# address_decoder_v2.net
KiCad netlist of a schematic drawn in EAGLE
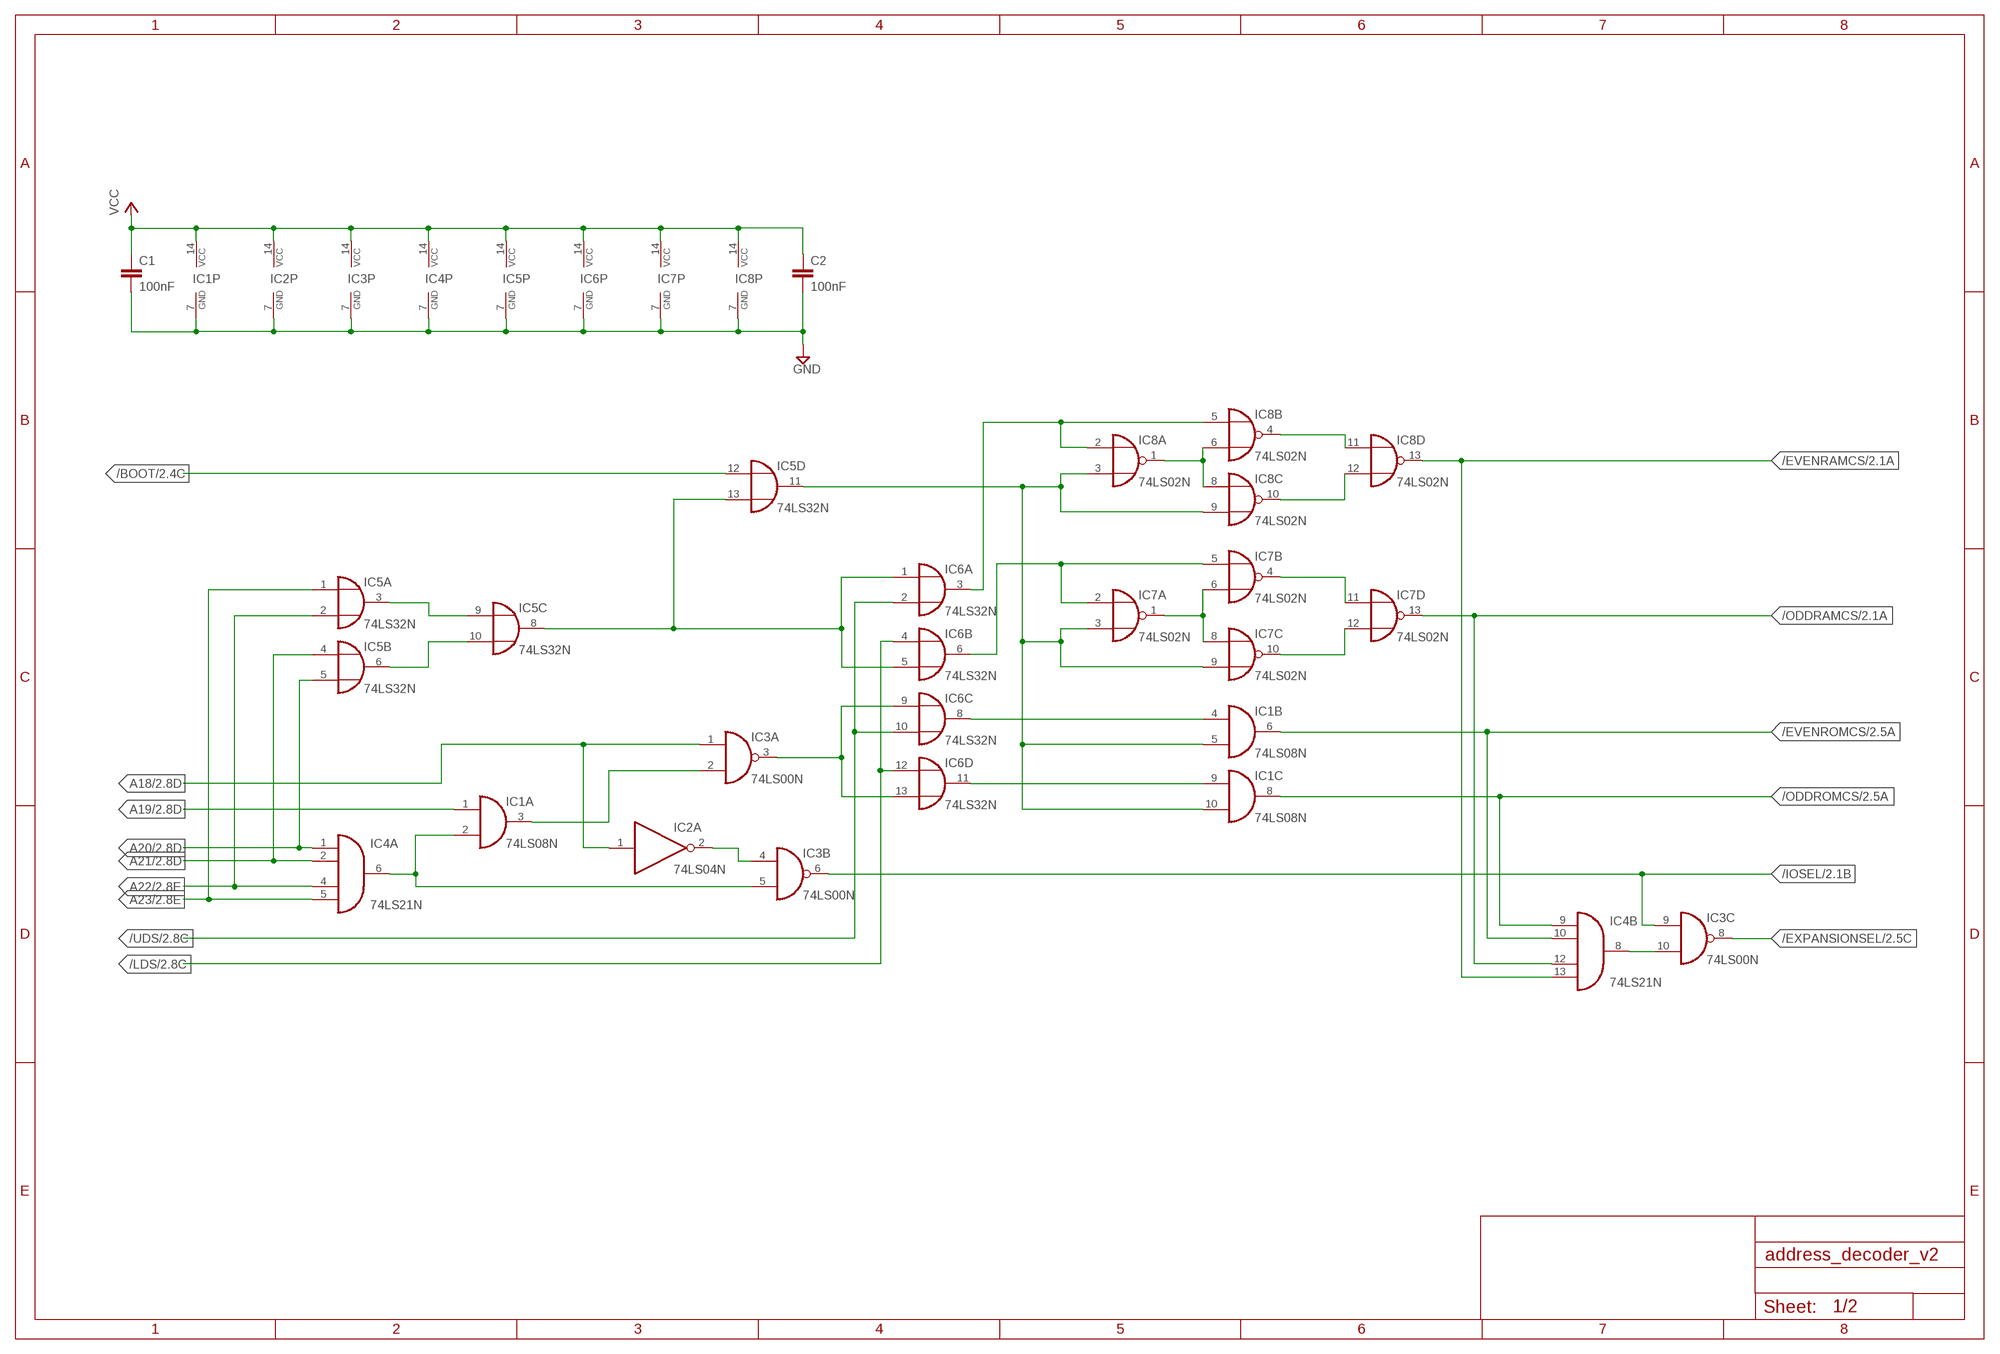
[diagram p0: schematic, sheet 1]
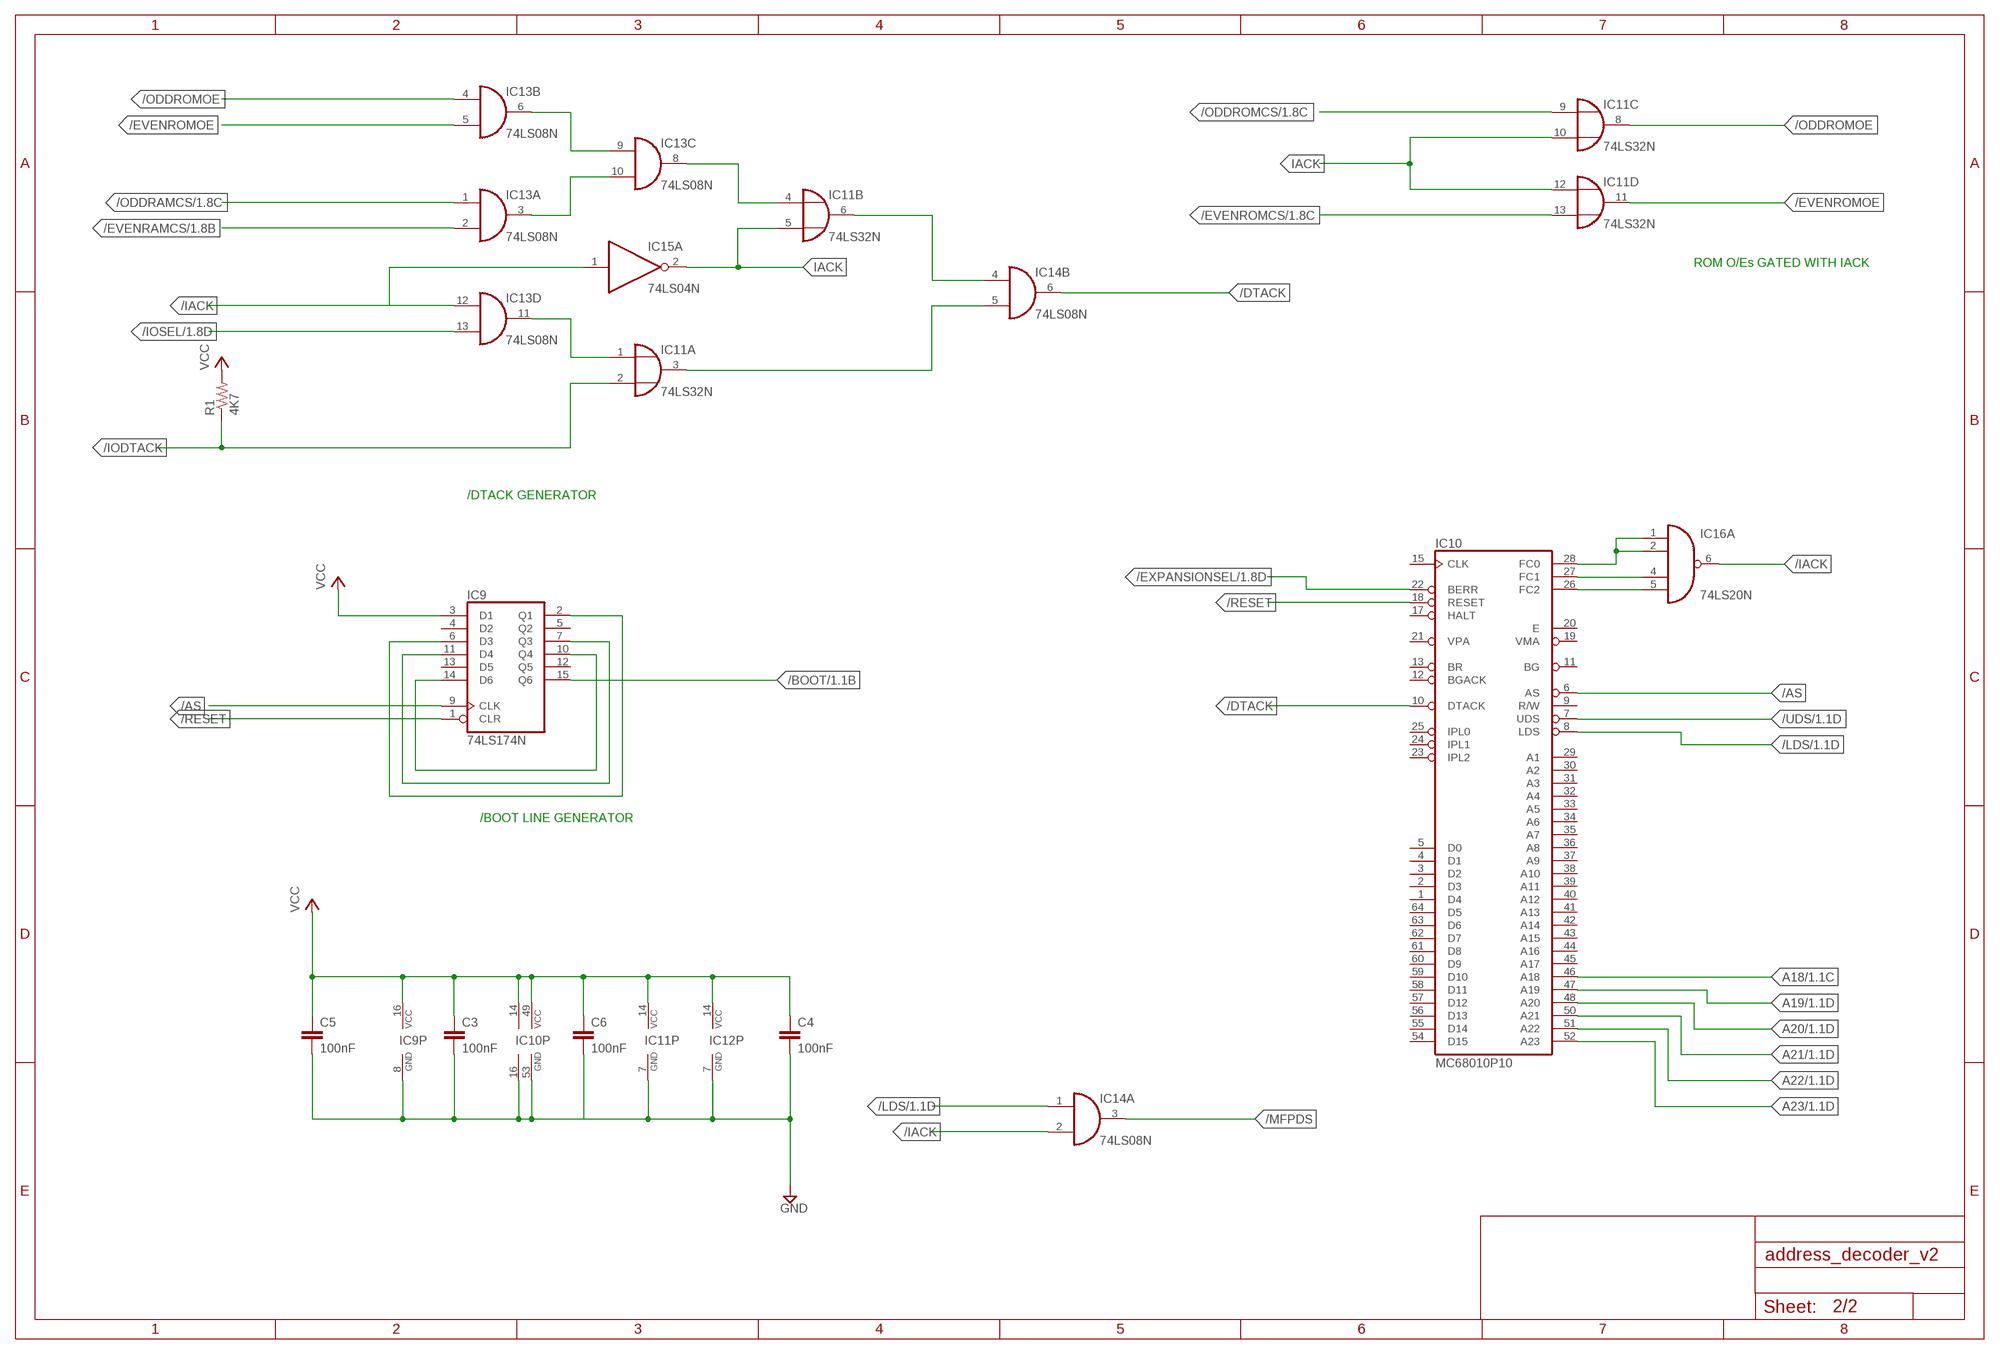
[diagram p1: schematic, sheet 2]

(export (version "E")
  (design (tool "Eeschema 10.0.6"))
  (components
    (comp (ref "C3")
      (value "100nF")
      (footprint "eagle-import:C5B3")
      (libsource (lib "eagle-import") (part "C5/3"))
    )
    (comp (ref "C4")
      (value "100nF")
      (footprint "eagle-import:C5B3")
      (libsource (lib "eagle-import") (part "C5/3"))
    )
    (comp (ref "C5")
      (value "100nF")
      (footprint "eagle-import:C5B3")
      (libsource (lib "eagle-import") (part "C5/3"))
    )
    (comp (ref "C6")
      (value "100nF")
      (footprint "eagle-import:C5B3")
      (libsource (lib "eagle-import") (part "C5/3"))
    )
    (comp (ref "IC9")
      (value "74LS174N")
      (footprint "eagle-import:DIL16")
      (libsource (lib "eagle-import") (part "74174NLS"))
    )
    (comp (ref "IC10")
      (value "MC68010P10")
      (footprint "eagle-import:DIL64")
      (libsource (lib "eagle-import") (part "MC68000P"))
    )
    (comp (ref "IC11")
      (value "74LS32N")
      (footprint "eagle-import:DIL14")
      (libsource (lib "eagle-import") (part "7432NLS"))
    )
    (comp (ref "IC12")
      (value "74LS21N")
      (footprint "eagle-import:DIL14")
      (libsource (lib "eagle-import") (part "7421NLS"))
    )
    (comp (ref "IC13")
      (value "74LS08N")
      (footprint "eagle-import:DIL14")
      (libsource (lib "eagle-import") (part "7408NLS"))
    )
    (comp (ref "IC14")
      (value "74LS08N")
      (footprint "eagle-import:DIL14")
      (libsource (lib "eagle-import") (part "7408NLS"))
    )
    (comp (ref "IC15")
      (value "74LS04N")
      (footprint "eagle-import:DIL14")
      (libsource (lib "eagle-import") (part "7404NLS"))
    )
    (comp (ref "IC16")
      (value "74LS20N")
      (footprint "eagle-import:DIL14")
      (libsource (lib "eagle-import") (part "7420NLS"))
    )
    (comp (ref "R1")
      (value "4K7")
      (footprint "eagle-import:0204_7")
      (libsource (lib "eagle-import") (part "R-US_0204/7"))
    )
    (comp (ref "C1")
      (value "100nF")
      (footprint "eagle-import:C025-024X044")
      (libsource (lib "eagle-import") (part "C-EU025-024X044"))
    )
    (comp (ref "C2")
      (value "100nF")
      (footprint "eagle-import:C025-024X044")
      (libsource (lib "eagle-import") (part "C-EU025-024X044"))
    )
    (comp (ref "IC1")
      (value "74LS08N")
      (footprint "eagle-import:DIL14")
      (fields (field (name "SPICEPREFIX") "I"))
      (libsource (lib "eagle-import") (part "7408NLS"))
    )
    (comp (ref "IC2")
      (value "74LS04N")
      (footprint "eagle-import:DIL14")
      (fields (field (name "SPICEPREFIX") "I"))
      (libsource (lib "eagle-import") (part "7404NLS"))
    )
    (comp (ref "IC3")
      (value "74LS00N")
      (footprint "eagle-import:DIL14")
      (libsource (lib "eagle-import") (part "7400NLS"))
    )
    (comp (ref "IC4")
      (value "74LS21N")
      (footprint "eagle-import:DIL14")
      (fields (field (name "SPICEPREFIX") "X"))
      (libsource (lib "eagle-import") (part "7421NLS"))
    )
    (comp (ref "IC5")
      (value "74LS32N")
      (footprint "eagle-import:DIL14")
      (fields (field (name "SPICEPREFIX") "J"))
      (libsource (lib "eagle-import") (part "7432NLS"))
    )
    (comp (ref "IC6")
      (value "74LS32N")
      (footprint "eagle-import:DIL14")
      (libsource (lib "eagle-import") (part "7432NLS"))
    )
    (comp (ref "IC7")
      (value "74LS02N")
      (footprint "eagle-import:DIL14")
      (libsource (lib "eagle-import") (part "7402NLS"))
    )
    (comp (ref "IC8")
      (value "74LS02N")
      (footprint "eagle-import:DIL14")
      (libsource (lib "eagle-import") (part "7402NLS"))
    )
  )
  (nets
    (net (code "1") (name "A18") (class "Default")
      (node (ref "IC10") (pin "46") (pinfunction "A18_46") (pintype "output"))
      (node (ref "IC2") (pin "1") (pinfunction "I_1") (pintype "input"))
      (node (ref "IC3") (pin "1") (pinfunction "I0_1") (pintype "input"))
    )
    (net (code "2") (name "A19") (class "Default")
      (node (ref "IC1") (pin "1") (pinfunction "I0_1") (pintype "input"))
      (node (ref "IC10") (pin "47") (pinfunction "A19_47") (pintype "output"))
    )
    (net (code "3") (name "A20") (class "Default")
      (node (ref "IC10") (pin "48") (pinfunction "A20_48") (pintype "output"))
      (node (ref "IC4") (pin "1") (pinfunction "I0_1") (pintype "input"))
      (node (ref "IC5") (pin "5") (pinfunction "I1_5") (pintype "input"))
    )
    (net (code "4") (name "A21") (class "Default")
      (node (ref "IC10") (pin "50") (pinfunction "A21_50") (pintype "output"))
      (node (ref "IC4") (pin "2") (pinfunction "I1_2") (pintype "input"))
      (node (ref "IC5") (pin "4") (pinfunction "I0_4") (pintype "input"))
    )
    (net (code "5") (name "A22") (class "Default")
      (node (ref "IC10") (pin "51") (pinfunction "A22_51") (pintype "output"))
      (node (ref "IC4") (pin "4") (pinfunction "I2_4") (pintype "input"))
      (node (ref "IC5") (pin "2") (pinfunction "I1_2") (pintype "input"))
    )
    (net (code "6") (name "A23") (class "Default")
      (node (ref "IC10") (pin "52") (pinfunction "A23_52") (pintype "output"))
      (node (ref "IC4") (pin "5") (pinfunction "I3_5") (pintype "input"))
      (node (ref "IC5") (pin "1") (pinfunction "I0_1") (pintype "input"))
    )
    (net (code "7") (name "GND") (class "Default")
      (node (ref "C1") (pin "2") (pinfunction "2_2") (pintype "passive"))
      (node (ref "C2") (pin "2") (pinfunction "2_2") (pintype "passive"))
      (node (ref "C3") (pin "2") (pinfunction "2_2") (pintype "passive"))
      (node (ref "C4") (pin "2") (pinfunction "2_2") (pintype "passive"))
      (node (ref "C5") (pin "2") (pinfunction "2_2") (pintype "passive"))
      (node (ref "IC1") (pin "7") (pinfunction "GND_7") (pintype "power_in"))
      (node (ref "IC10") (pin "16") (pinfunction "GND_16") (pintype "power_in"))
      (node (ref "IC10") (pin "53") (pinfunction "GND_53") (pintype "power_in"))
      (node (ref "IC11") (pin "7") (pinfunction "GND_7") (pintype "power_in"))
      (node (ref "IC12") (pin "7") (pinfunction "GND_7") (pintype "power_in"))
      (node (ref "IC2") (pin "7") (pinfunction "GND_7") (pintype "power_in"))
      (node (ref "IC3") (pin "7") (pinfunction "GND_7") (pintype "power_in"))
      (node (ref "IC4") (pin "7") (pinfunction "GND_7") (pintype "power_in"))
      (node (ref "IC5") (pin "7") (pinfunction "GND_7") (pintype "power_in"))
      (node (ref "IC6") (pin "7") (pinfunction "GND_7") (pintype "power_in"))
      (node (ref "IC7") (pin "7") (pinfunction "GND_7") (pintype "power_in"))
      (node (ref "IC8") (pin "7") (pinfunction "GND_7") (pintype "power_in"))
      (node (ref "IC9") (pin "8") (pinfunction "GND_8") (pintype "power_in"))
    )
    (net (code "8") (name "IACK") (class "Default")
      (node (ref "IC11") (pin "10") (pinfunction "I1_10") (pintype "input"))
      (node (ref "IC11") (pin "12") (pinfunction "I0_12") (pintype "input"))
      (node (ref "IC11") (pin "5") (pinfunction "I1_5") (pintype "input"))
      (node (ref "IC15") (pin "2") (pinfunction "O_2") (pintype "output"))
    )
    (net (code "9") (name "Net-(IC1A-I1)") (class "Default")
      (node (ref "IC1") (pin "2") (pinfunction "I1_2") (pintype "input"))
      (node (ref "IC3") (pin "5") (pinfunction "I1_5") (pintype "input"))
      (node (ref "IC4") (pin "6") (pinfunction "O_6") (pintype "output"))
    )
    (net (code "10") (name "Net-(IC1A-O)") (class "Default")
      (node (ref "IC1") (pin "3") (pinfunction "O_3") (pintype "output"))
      (node (ref "IC3") (pin "2") (pinfunction "I1_2") (pintype "input"))
    )
    (net (code "11") (name "Net-(IC1B-I0)") (class "Default")
      (node (ref "IC1") (pin "4") (pinfunction "I0_4") (pintype "input"))
      (node (ref "IC6") (pin "8") (pinfunction "O_8") (pintype "output"))
    )
    (net (code "12") (name "Net-(IC1B-I1)") (class "Default")
      (node (ref "IC1") (pin "10") (pinfunction "I1_10") (pintype "input"))
      (node (ref "IC1") (pin "5") (pinfunction "I1_5") (pintype "input"))
      (node (ref "IC5") (pin "11") (pinfunction "O_11") (pintype "output"))
      (node (ref "IC7") (pin "3") (pinfunction "I1_3") (pintype "input"))
      (node (ref "IC7") (pin "9") (pinfunction "I1_9") (pintype "input"))
      (node (ref "IC8") (pin "3") (pinfunction "I1_3") (pintype "input"))
      (node (ref "IC8") (pin "9") (pinfunction "I1_9") (pintype "input"))
    )
    (net (code "13") (name "Net-(IC1C-I0)") (class "Default")
      (node (ref "IC1") (pin "9") (pinfunction "I0_9") (pintype "input"))
      (node (ref "IC6") (pin "11") (pinfunction "O_11") (pintype "output"))
    )
    (net (code "14") (name "Net-(IC2A-O)") (class "Default")
      (node (ref "IC2") (pin "2") (pinfunction "O_2") (pintype "output"))
      (node (ref "IC3") (pin "4") (pinfunction "I0_4") (pintype "input"))
    )
    (net (code "15") (name "Net-(IC3A-O)") (class "Default")
      (node (ref "IC3") (pin "3") (pinfunction "O_3") (pintype "output"))
      (node (ref "IC6") (pin "13") (pinfunction "I1_13") (pintype "input"))
      (node (ref "IC6") (pin "9") (pinfunction "I0_9") (pintype "input"))
    )
    (net (code "16") (name "Net-(IC3C-I1)") (class "Default")
      (node (ref "IC3") (pin "10") (pinfunction "I1_10") (pintype "input"))
      (node (ref "IC4") (pin "8") (pinfunction "O_8") (pintype "output"))
    )
    (net (code "17") (name "Net-(IC5A-O)") (class "Default")
      (node (ref "IC5") (pin "3") (pinfunction "O_3") (pintype "output"))
      (node (ref "IC5") (pin "9") (pinfunction "I0_9") (pintype "input"))
    )
    (net (code "18") (name "Net-(IC5B-O)") (class "Default")
      (node (ref "IC5") (pin "10") (pinfunction "I1_10") (pintype "input"))
      (node (ref "IC5") (pin "6") (pinfunction "O_6") (pintype "output"))
    )
    (net (code "19") (name "Net-(IC5C-O)") (class "Default")
      (node (ref "IC5") (pin "13") (pinfunction "I1_13") (pintype "input"))
      (node (ref "IC5") (pin "8") (pinfunction "O_8") (pintype "output"))
      (node (ref "IC6") (pin "1") (pinfunction "I0_1") (pintype "input"))
      (node (ref "IC6") (pin "5") (pinfunction "I1_5") (pintype "input"))
    )
    (net (code "20") (name "Net-(IC6A-O)") (class "Default")
      (node (ref "IC6") (pin "3") (pinfunction "O_3") (pintype "output"))
      (node (ref "IC8") (pin "2") (pinfunction "I0_2") (pintype "input"))
      (node (ref "IC8") (pin "5") (pinfunction "I0_5") (pintype "input"))
    )
    (net (code "21") (name "Net-(IC6B-O)") (class "Default")
      (node (ref "IC6") (pin "6") (pinfunction "O_6") (pintype "output"))
      (node (ref "IC7") (pin "2") (pinfunction "I0_2") (pintype "input"))
      (node (ref "IC7") (pin "5") (pinfunction "I0_5") (pintype "input"))
    )
    (net (code "22") (name "Net-(IC7A-O)") (class "Default")
      (node (ref "IC7") (pin "1") (pinfunction "O_1") (pintype "output"))
      (node (ref "IC7") (pin "6") (pinfunction "I1_6") (pintype "input"))
      (node (ref "IC7") (pin "8") (pinfunction "I0_8") (pintype "input"))
    )
    (net (code "23") (name "Net-(IC7B-O)") (class "Default")
      (node (ref "IC7") (pin "11") (pinfunction "I0_11") (pintype "input"))
      (node (ref "IC7") (pin "4") (pinfunction "O_4") (pintype "output"))
    )
    (net (code "24") (name "Net-(IC7C-O)") (class "Default")
      (node (ref "IC7") (pin "10") (pinfunction "O_10") (pintype "output"))
      (node (ref "IC7") (pin "12") (pinfunction "I1_12") (pintype "input"))
    )
    (net (code "25") (name "Net-(IC8A-O)") (class "Default")
      (node (ref "IC8") (pin "1") (pinfunction "O_1") (pintype "output"))
      (node (ref "IC8") (pin "6") (pinfunction "I1_6") (pintype "input"))
      (node (ref "IC8") (pin "8") (pinfunction "I0_8") (pintype "input"))
    )
    (net (code "26") (name "Net-(IC8B-O)") (class "Default")
      (node (ref "IC8") (pin "11") (pinfunction "I0_11") (pintype "input"))
      (node (ref "IC8") (pin "4") (pinfunction "O_4") (pintype "output"))
    )
    (net (code "27") (name "Net-(IC8C-O)") (class "Default")
      (node (ref "IC8") (pin "10") (pinfunction "O_10") (pintype "output"))
      (node (ref "IC8") (pin "12") (pinfunction "I1_12") (pintype "input"))
    )
    (net (code "28") (name "Net-(IC9A-D3)") (class "Default")
      (node (ref "IC9") (pin "2") (pinfunction "Q1_2") (pintype "output"))
      (node (ref "IC9") (pin "6") (pinfunction "D3_6") (pintype "input"))
    )
    (net (code "29") (name "Net-(IC9A-D4)") (class "Default")
      (node (ref "IC9") (pin "11") (pinfunction "D4_11") (pintype "input"))
      (node (ref "IC9") (pin "7") (pinfunction "Q3_7") (pintype "output"))
    )
    (net (code "30") (name "Net-(IC9A-D6)") (class "Default")
      (node (ref "IC9") (pin "10") (pinfunction "Q4_10") (pintype "output"))
      (node (ref "IC9") (pin "14") (pinfunction "D6_14") (pintype "input"))
    )
    (net (code "31") (name "Net-(IC10A-FC0)") (class "Default")
      (node (ref "IC10") (pin "28") (pinfunction "FC0_28") (pintype "output"))
      (node (ref "IC16") (pin "1") (pinfunction "I0_1") (pintype "input"))
      (node (ref "IC16") (pin "2") (pinfunction "I1_2") (pintype "input"))
    )
    (net (code "32") (name "Net-(IC10A-FC1)") (class "Default")
      (node (ref "IC10") (pin "27") (pinfunction "FC1_27") (pintype "output"))
      (node (ref "IC16") (pin "4") (pinfunction "I2_4") (pintype "input"))
    )
    (net (code "33") (name "Net-(IC10A-FC2)") (class "Default")
      (node (ref "IC10") (pin "26") (pinfunction "FC2_26") (pintype "output"))
      (node (ref "IC16") (pin "5") (pinfunction "I3_5") (pintype "input"))
    )
    (net (code "34") (name "Net-(IC11A-I0)") (class "Default")
      (node (ref "IC11") (pin "1") (pinfunction "I0_1") (pintype "input"))
      (node (ref "IC13") (pin "11") (pinfunction "O_11") (pintype "output"))
    )
    (net (code "35") (name "Net-(IC11A-O)") (class "Default")
      (node (ref "IC11") (pin "3") (pinfunction "O_3") (pintype "output"))
      (node (ref "IC14") (pin "5") (pinfunction "I1_5") (pintype "input"))
    )
    (net (code "36") (name "Net-(IC11B-I0)") (class "Default")
      (node (ref "IC11") (pin "4") (pinfunction "I0_4") (pintype "input"))
      (node (ref "IC13") (pin "8") (pinfunction "O_8") (pintype "output"))
    )
    (net (code "37") (name "Net-(IC11B-O)") (class "Default")
      (node (ref "IC11") (pin "6") (pinfunction "O_6") (pintype "output"))
      (node (ref "IC14") (pin "4") (pinfunction "I0_4") (pintype "input"))
    )
    (net (code "38") (name "Net-(IC13A-O)") (class "Default")
      (node (ref "IC13") (pin "10") (pinfunction "I1_10") (pintype "input"))
      (node (ref "IC13") (pin "3") (pinfunction "O_3") (pintype "output"))
    )
    (net (code "39") (name "Net-(IC13B-O)") (class "Default")
      (node (ref "IC13") (pin "6") (pinfunction "O_6") (pintype "output"))
      (node (ref "IC13") (pin "9") (pinfunction "I0_9") (pintype "input"))
    )
    (net (code "40") (name "VCC") (class "Default")
      (node (ref "C1") (pin "1") (pinfunction "1_1") (pintype "passive"))
      (node (ref "C2") (pin "1") (pinfunction "1_1") (pintype "passive"))
      (node (ref "C3") (pin "1") (pinfunction "1_1") (pintype "passive"))
      (node (ref "C4") (pin "1") (pinfunction "1_1") (pintype "passive"))
      (node (ref "C5") (pin "1") (pinfunction "1_1") (pintype "passive"))
      (node (ref "C6") (pin "1") (pinfunction "1_1") (pintype "passive"))
      (node (ref "IC1") (pin "14") (pinfunction "VCC_14") (pintype "power_in"))
      (node (ref "IC10") (pin "14") (pinfunction "VCC_14") (pintype "power_in"))
      (node (ref "IC10") (pin "49") (pinfunction "VCC_49") (pintype "power_in"))
      (node (ref "IC11") (pin "14") (pinfunction "VCC_14") (pintype "power_in"))
      (node (ref "IC12") (pin "14") (pinfunction "VCC_14") (pintype "power_in"))
      (node (ref "IC2") (pin "14") (pinfunction "VCC_14") (pintype "power_in"))
      (node (ref "IC3") (pin "14") (pinfunction "VCC_14") (pintype "power_in"))
      (node (ref "IC4") (pin "14") (pinfunction "VCC_14") (pintype "power_in"))
      (node (ref "IC5") (pin "14") (pinfunction "VCC_14") (pintype "power_in"))
      (node (ref "IC6") (pin "14") (pinfunction "VCC_14") (pintype "power_in"))
      (node (ref "IC7") (pin "14") (pinfunction "VCC_14") (pintype "power_in"))
      (node (ref "IC8") (pin "14") (pinfunction "VCC_14") (pintype "power_in"))
      (node (ref "IC9") (pin "16") (pinfunction "VCC_16") (pintype "power_in"))
      (node (ref "IC9") (pin "3") (pinfunction "D1_3") (pintype "input"))
      (node (ref "R1") (pin "2") (pinfunction "2_2") (pintype "passive"))
    )
    (net (code "41") (name "unconnected-(C6-Pad2)") (class "Default")
      (node (ref "C6") (pin "2") (pinfunction "2_2") (pintype "passive"))
    )
    (net (code "42") (name "unconnected-(IC9A-D2-Pad4)") (class "Default")
      (node (ref "IC9") (pin "4") (pinfunction "D2_4") (pintype "input"))
    )
    (net (code "43") (name "unconnected-(IC9A-D5-Pad13)") (class "Default")
      (node (ref "IC9") (pin "13") (pinfunction "D5_13") (pintype "input"))
    )
    (net (code "44") (name "unconnected-(IC9A-Q2-Pad5)") (class "Default")
      (node (ref "IC9") (pin "5") (pinfunction "Q2_5") (pintype "output"))
    )
    (net (code "45") (name "unconnected-(IC9A-Q5-Pad12)") (class "Default")
      (node (ref "IC9") (pin "12") (pinfunction "Q5_12") (pintype "output"))
    )
    (net (code "46") (name "unconnected-(IC10A-A1-Pad29)") (class "Default")
      (node (ref "IC10") (pin "29") (pinfunction "A1_29") (pintype "output"))
    )
    (net (code "47") (name "unconnected-(IC10A-A2-Pad30)") (class "Default")
      (node (ref "IC10") (pin "30") (pinfunction "A2_30") (pintype "output"))
    )
    (net (code "48") (name "unconnected-(IC10A-A3-Pad31)") (class "Default")
      (node (ref "IC10") (pin "31") (pinfunction "A3_31") (pintype "output"))
    )
    (net (code "49") (name "unconnected-(IC10A-A4-Pad32)") (class "Default")
      (node (ref "IC10") (pin "32") (pinfunction "A4_32") (pintype "output"))
    )
    (net (code "50") (name "unconnected-(IC10A-A5-Pad33)") (class "Default")
      (node (ref "IC10") (pin "33") (pinfunction "A5_33") (pintype "output"))
    )
    (net (code "51") (name "unconnected-(IC10A-A6-Pad34)") (class "Default")
      (node (ref "IC10") (pin "34") (pinfunction "A6_34") (pintype "output"))
    )
    (net (code "52") (name "unconnected-(IC10A-A7-Pad35)") (class "Default")
      (node (ref "IC10") (pin "35") (pinfunction "A7_35") (pintype "output"))
    )
    (net (code "53") (name "unconnected-(IC10A-A8-Pad36)") (class "Default")
      (node (ref "IC10") (pin "36") (pinfunction "A8_36") (pintype "output"))
    )
    (net (code "54") (name "unconnected-(IC10A-A9-Pad37)") (class "Default")
      (node (ref "IC10") (pin "37") (pinfunction "A9_37") (pintype "output"))
    )
    (net (code "55") (name "unconnected-(IC10A-A10-Pad38)") (class "Default")
      (node (ref "IC10") (pin "38") (pinfunction "A10_38") (pintype "output"))
    )
    (net (code "56") (name "unconnected-(IC10A-A11-Pad39)") (class "Default")
      (node (ref "IC10") (pin "39") (pinfunction "A11_39") (pintype "output"))
    )
    (net (code "57") (name "unconnected-(IC10A-A12-Pad40)") (class "Default")
      (node (ref "IC10") (pin "40") (pinfunction "A12_40") (pintype "output"))
    )
    (net (code "58") (name "unconnected-(IC10A-A13-Pad41)") (class "Default")
      (node (ref "IC10") (pin "41") (pinfunction "A13_41") (pintype "output"))
    )
    (net (code "59") (name "unconnected-(IC10A-A14-Pad42)") (class "Default")
      (node (ref "IC10") (pin "42") (pinfunction "A14_42") (pintype "output"))
    )
    (net (code "60") (name "unconnected-(IC10A-A15-Pad43)") (class "Default")
      (node (ref "IC10") (pin "43") (pinfunction "A15_43") (pintype "output"))
    )
    (net (code "61") (name "unconnected-(IC10A-A16-Pad44)") (class "Default")
      (node (ref "IC10") (pin "44") (pinfunction "A16_44") (pintype "output"))
    )
    (net (code "62") (name "unconnected-(IC10A-A17-Pad45)") (class "Default")
      (node (ref "IC10") (pin "45") (pinfunction "A17_45") (pintype "output"))
    )
    (net (code "63") (name "unconnected-(IC10A-BG-Pad11)") (class "Default")
      (node (ref "IC10") (pin "11") (pinfunction "BG_11") (pintype "output"))
    )
    (net (code "64") (name "unconnected-(IC10A-BGACK-Pad12)") (class "Default")
      (node (ref "IC10") (pin "12") (pinfunction "BGACK_12") (pintype "input"))
    )
    (net (code "65") (name "unconnected-(IC10A-BR-Pad13)") (class "Default")
      (node (ref "IC10") (pin "13") (pinfunction "BR_13") (pintype "input"))
    )
    (net (code "66") (name "unconnected-(IC10A-CLK-Pad15)") (class "Default")
      (node (ref "IC10") (pin "15") (pinfunction "CLK_15") (pintype "input"))
    )
    (net (code "67") (name "unconnected-(IC10A-D0-Pad5)") (class "Default")
      (node (ref "IC10") (pin "5") (pinfunction "D0_5") (pintype "bidirectional"))
    )
    (net (code "68") (name "unconnected-(IC10A-D1-Pad4)") (class "Default")
      (node (ref "IC10") (pin "4") (pinfunction "D1_4") (pintype "bidirectional"))
    )
    (net (code "69") (name "unconnected-(IC10A-D2-Pad3)") (class "Default")
      (node (ref "IC10") (pin "3") (pinfunction "D2_3") (pintype "bidirectional"))
    )
    (net (code "70") (name "unconnected-(IC10A-D3-Pad2)") (class "Default")
      (node (ref "IC10") (pin "2") (pinfunction "D3_2") (pintype "bidirectional"))
    )
    (net (code "71") (name "unconnected-(IC10A-D4-Pad1)") (class "Default")
      (node (ref "IC10") (pin "1") (pinfunction "D4_1") (pintype "bidirectional"))
    )
    (net (code "72") (name "unconnected-(IC10A-D5-Pad64)") (class "Default")
      (node (ref "IC10") (pin "64") (pinfunction "D5_64") (pintype "bidirectional"))
    )
    (net (code "73") (name "unconnected-(IC10A-D6-Pad63)") (class "Default")
      (node (ref "IC10") (pin "63") (pinfunction "D6_63") (pintype "bidirectional"))
    )
    (net (code "74") (name "unconnected-(IC10A-D7-Pad62)") (class "Default")
      (node (ref "IC10") (pin "62") (pinfunction "D7_62") (pintype "bidirectional"))
    )
    (net (code "75") (name "unconnected-(IC10A-D8-Pad61)") (class "Default")
      (node (ref "IC10") (pin "61") (pinfunction "D8_61") (pintype "bidirectional"))
    )
    (net (code "76") (name "unconnected-(IC10A-D9-Pad60)") (class "Default")
      (node (ref "IC10") (pin "60") (pinfunction "D9_60") (pintype "bidirectional"))
    )
    (net (code "77") (name "unconnected-(IC10A-D10-Pad59)") (class "Default")
      (node (ref "IC10") (pin "59") (pinfunction "D10_59") (pintype "bidirectional"))
    )
    (net (code "78") (name "unconnected-(IC10A-D11-Pad58)") (class "Default")
      (node (ref "IC10") (pin "58") (pinfunction "D11_58") (pintype "bidirectional"))
    )
    (net (code "79") (name "unconnected-(IC10A-D12-Pad57)") (class "Default")
      (node (ref "IC10") (pin "57") (pinfunction "D12_57") (pintype "bidirectional"))
    )
    (net (code "80") (name "unconnected-(IC10A-D13-Pad56)") (class "Default")
      (node (ref "IC10") (pin "56") (pinfunction "D13_56") (pintype "bidirectional"))
    )
    (net (code "81") (name "unconnected-(IC10A-D14-Pad55)") (class "Default")
      (node (ref "IC10") (pin "55") (pinfunction "D14_55") (pintype "bidirectional"))
    )
    (net (code "82") (name "unconnected-(IC10A-D15-Pad54)") (class "Default")
      (node (ref "IC10") (pin "54") (pinfunction "D15_54") (pintype "bidirectional"))
    )
    (net (code "83") (name "unconnected-(IC10A-E-Pad20)") (class "Default")
      (node (ref "IC10") (pin "20") (pinfunction "E_20") (pintype "output"))
    )
    (net (code "84") (name "unconnected-(IC10A-HALT-Pad17)") (class "Default")
      (node (ref "IC10") (pin "17") (pinfunction "HALT_17") (pintype "bidirectional"))
    )
    (net (code "85") (name "unconnected-(IC10A-IPL0-Pad25)") (class "Default")
      (node (ref "IC10") (pin "25") (pinfunction "IPL0_25") (pintype "input"))
    )
    (net (code "86") (name "unconnected-(IC10A-IPL1-Pad24)") (class "Default")
      (node (ref "IC10") (pin "24") (pinfunction "IPL1_24") (pintype "input"))
    )
    (net (code "87") (name "unconnected-(IC10A-IPL2-Pad23)") (class "Default")
      (node (ref "IC10") (pin "23") (pinfunction "IPL2_23") (pintype "input"))
    )
    (net (code "88") (name "unconnected-(IC10A-R{slash}W-Pad9)") (class "Default")
      (node (ref "IC10") (pin "9") (pinfunction "R/W_9") (pintype "output"))
    )
    (net (code "89") (name "unconnected-(IC10A-VMA-Pad19)") (class "Default")
      (node (ref "IC10") (pin "19") (pinfunction "VMA_19") (pintype "output"))
    )
    (net (code "90") (name "unconnected-(IC10A-VPA-Pad21)") (class "Default")
      (node (ref "IC10") (pin "21") (pinfunction "VPA_21") (pintype "input"))
    )
    (net (code "91") (name "{slash}AS") (class "Default")
      (node (ref "IC10") (pin "6") (pinfunction "AS_6") (pintype "output"))
      (node (ref "IC9") (pin "9") (pinfunction "CLK_9") (pintype "input"))
    )
    (net (code "92") (name "{slash}BOOT") (class "Default")
      (node (ref "IC5") (pin "12") (pinfunction "I0_12") (pintype "input"))
      (node (ref "IC9") (pin "15") (pinfunction "Q6_15") (pintype "output"))
    )
    (net (code "93") (name "{slash}DTACK") (class "Default")
      (node (ref "IC10") (pin "10") (pinfunction "DTACK_10") (pintype "input"))
      (node (ref "IC14") (pin "6") (pinfunction "O_6") (pintype "output"))
    )
    (net (code "94") (name "{slash}EVENRAMCS") (class "Default")
      (node (ref "IC13") (pin "2") (pinfunction "I1_2") (pintype "input"))
      (node (ref "IC4") (pin "13") (pinfunction "I3_13") (pintype "input"))
      (node (ref "IC8") (pin "13") (pinfunction "O_13") (pintype "output"))
    )
    (net (code "95") (name "{slash}EVENROMCS") (class "Default")
      (node (ref "IC1") (pin "6") (pinfunction "O_6") (pintype "output"))
      (node (ref "IC11") (pin "13") (pinfunction "I1_13") (pintype "input"))
      (node (ref "IC4") (pin "10") (pinfunction "I1_10") (pintype "input"))
    )
    (net (code "96") (name "{slash}EVENROMOE") (class "Default")
      (node (ref "IC11") (pin "11") (pinfunction "O_11") (pintype "output"))
      (node (ref "IC13") (pin "5") (pinfunction "I1_5") (pintype "input"))
    )
    (net (code "97") (name "{slash}EXPANSIONSEL") (class "Default")
      (node (ref "IC10") (pin "22") (pinfunction "BERR_22") (pintype "input"))
      (node (ref "IC3") (pin "8") (pinfunction "O_8") (pintype "output"))
    )
    (net (code "98") (name "{slash}IACK") (class "Default")
      (node (ref "IC13") (pin "12") (pinfunction "I0_12") (pintype "input"))
      (node (ref "IC14") (pin "2") (pinfunction "I1_2") (pintype "input"))
      (node (ref "IC15") (pin "1") (pinfunction "I_1") (pintype "input"))
      (node (ref "IC16") (pin "6") (pinfunction "O_6") (pintype "output"))
    )
    (net (code "99") (name "{slash}IODTACK") (class "Default")
      (node (ref "IC11") (pin "2") (pinfunction "I1_2") (pintype "input"))
      (node (ref "R1") (pin "1") (pinfunction "1_1") (pintype "passive"))
    )
    (net (code "100") (name "{slash}IOSEL") (class "Default")
      (node (ref "IC13") (pin "13") (pinfunction "I1_13") (pintype "input"))
      (node (ref "IC3") (pin "6") (pinfunction "O_6") (pintype "output"))
      (node (ref "IC3") (pin "9") (pinfunction "I0_9") (pintype "input"))
    )
    (net (code "101") (name "{slash}LDS") (class "Default")
      (node (ref "IC10") (pin "8") (pinfunction "LDS_8") (pintype "output"))
      (node (ref "IC14") (pin "1") (pinfunction "I0_1") (pintype "input"))
      (node (ref "IC6") (pin "12") (pinfunction "I0_12") (pintype "input"))
      (node (ref "IC6") (pin "4") (pinfunction "I0_4") (pintype "input"))
    )
    (net (code "102") (name "{slash}MFPDS") (class "Default")
      (node (ref "IC14") (pin "3") (pinfunction "O_3") (pintype "output"))
    )
    (net (code "103") (name "{slash}ODDRAMCS") (class "Default")
      (node (ref "IC13") (pin "1") (pinfunction "I0_1") (pintype "input"))
      (node (ref "IC4") (pin "12") (pinfunction "I2_12") (pintype "input"))
      (node (ref "IC7") (pin "13") (pinfunction "O_13") (pintype "output"))
    )
    (net (code "104") (name "{slash}ODDROMCS") (class "Default")
      (node (ref "IC1") (pin "8") (pinfunction "O_8") (pintype "output"))
      (node (ref "IC11") (pin "9") (pinfunction "I0_9") (pintype "input"))
      (node (ref "IC4") (pin "9") (pinfunction "I0_9") (pintype "input"))
    )
    (net (code "105") (name "{slash}ODDROMOE") (class "Default")
      (node (ref "IC11") (pin "8") (pinfunction "O_8") (pintype "output"))
      (node (ref "IC13") (pin "4") (pinfunction "I0_4") (pintype "input"))
    )
    (net (code "106") (name "{slash}RESET") (class "Default")
      (node (ref "IC10") (pin "18") (pinfunction "RESET_18") (pintype "bidirectional"))
      (node (ref "IC9") (pin "1") (pinfunction "CLR_1") (pintype "input"))
    )
    (net (code "107") (name "{slash}UDS") (class "Default")
      (node (ref "IC10") (pin "7") (pinfunction "UDS_7") (pintype "output"))
      (node (ref "IC6") (pin "10") (pinfunction "I1_10") (pintype "input"))
      (node (ref "IC6") (pin "2") (pinfunction "I1_2") (pintype "input"))
    )
  )
)
